# PI_SCH_HDMI.net
KiCad netlist of a schematic drawn in EasyEDA
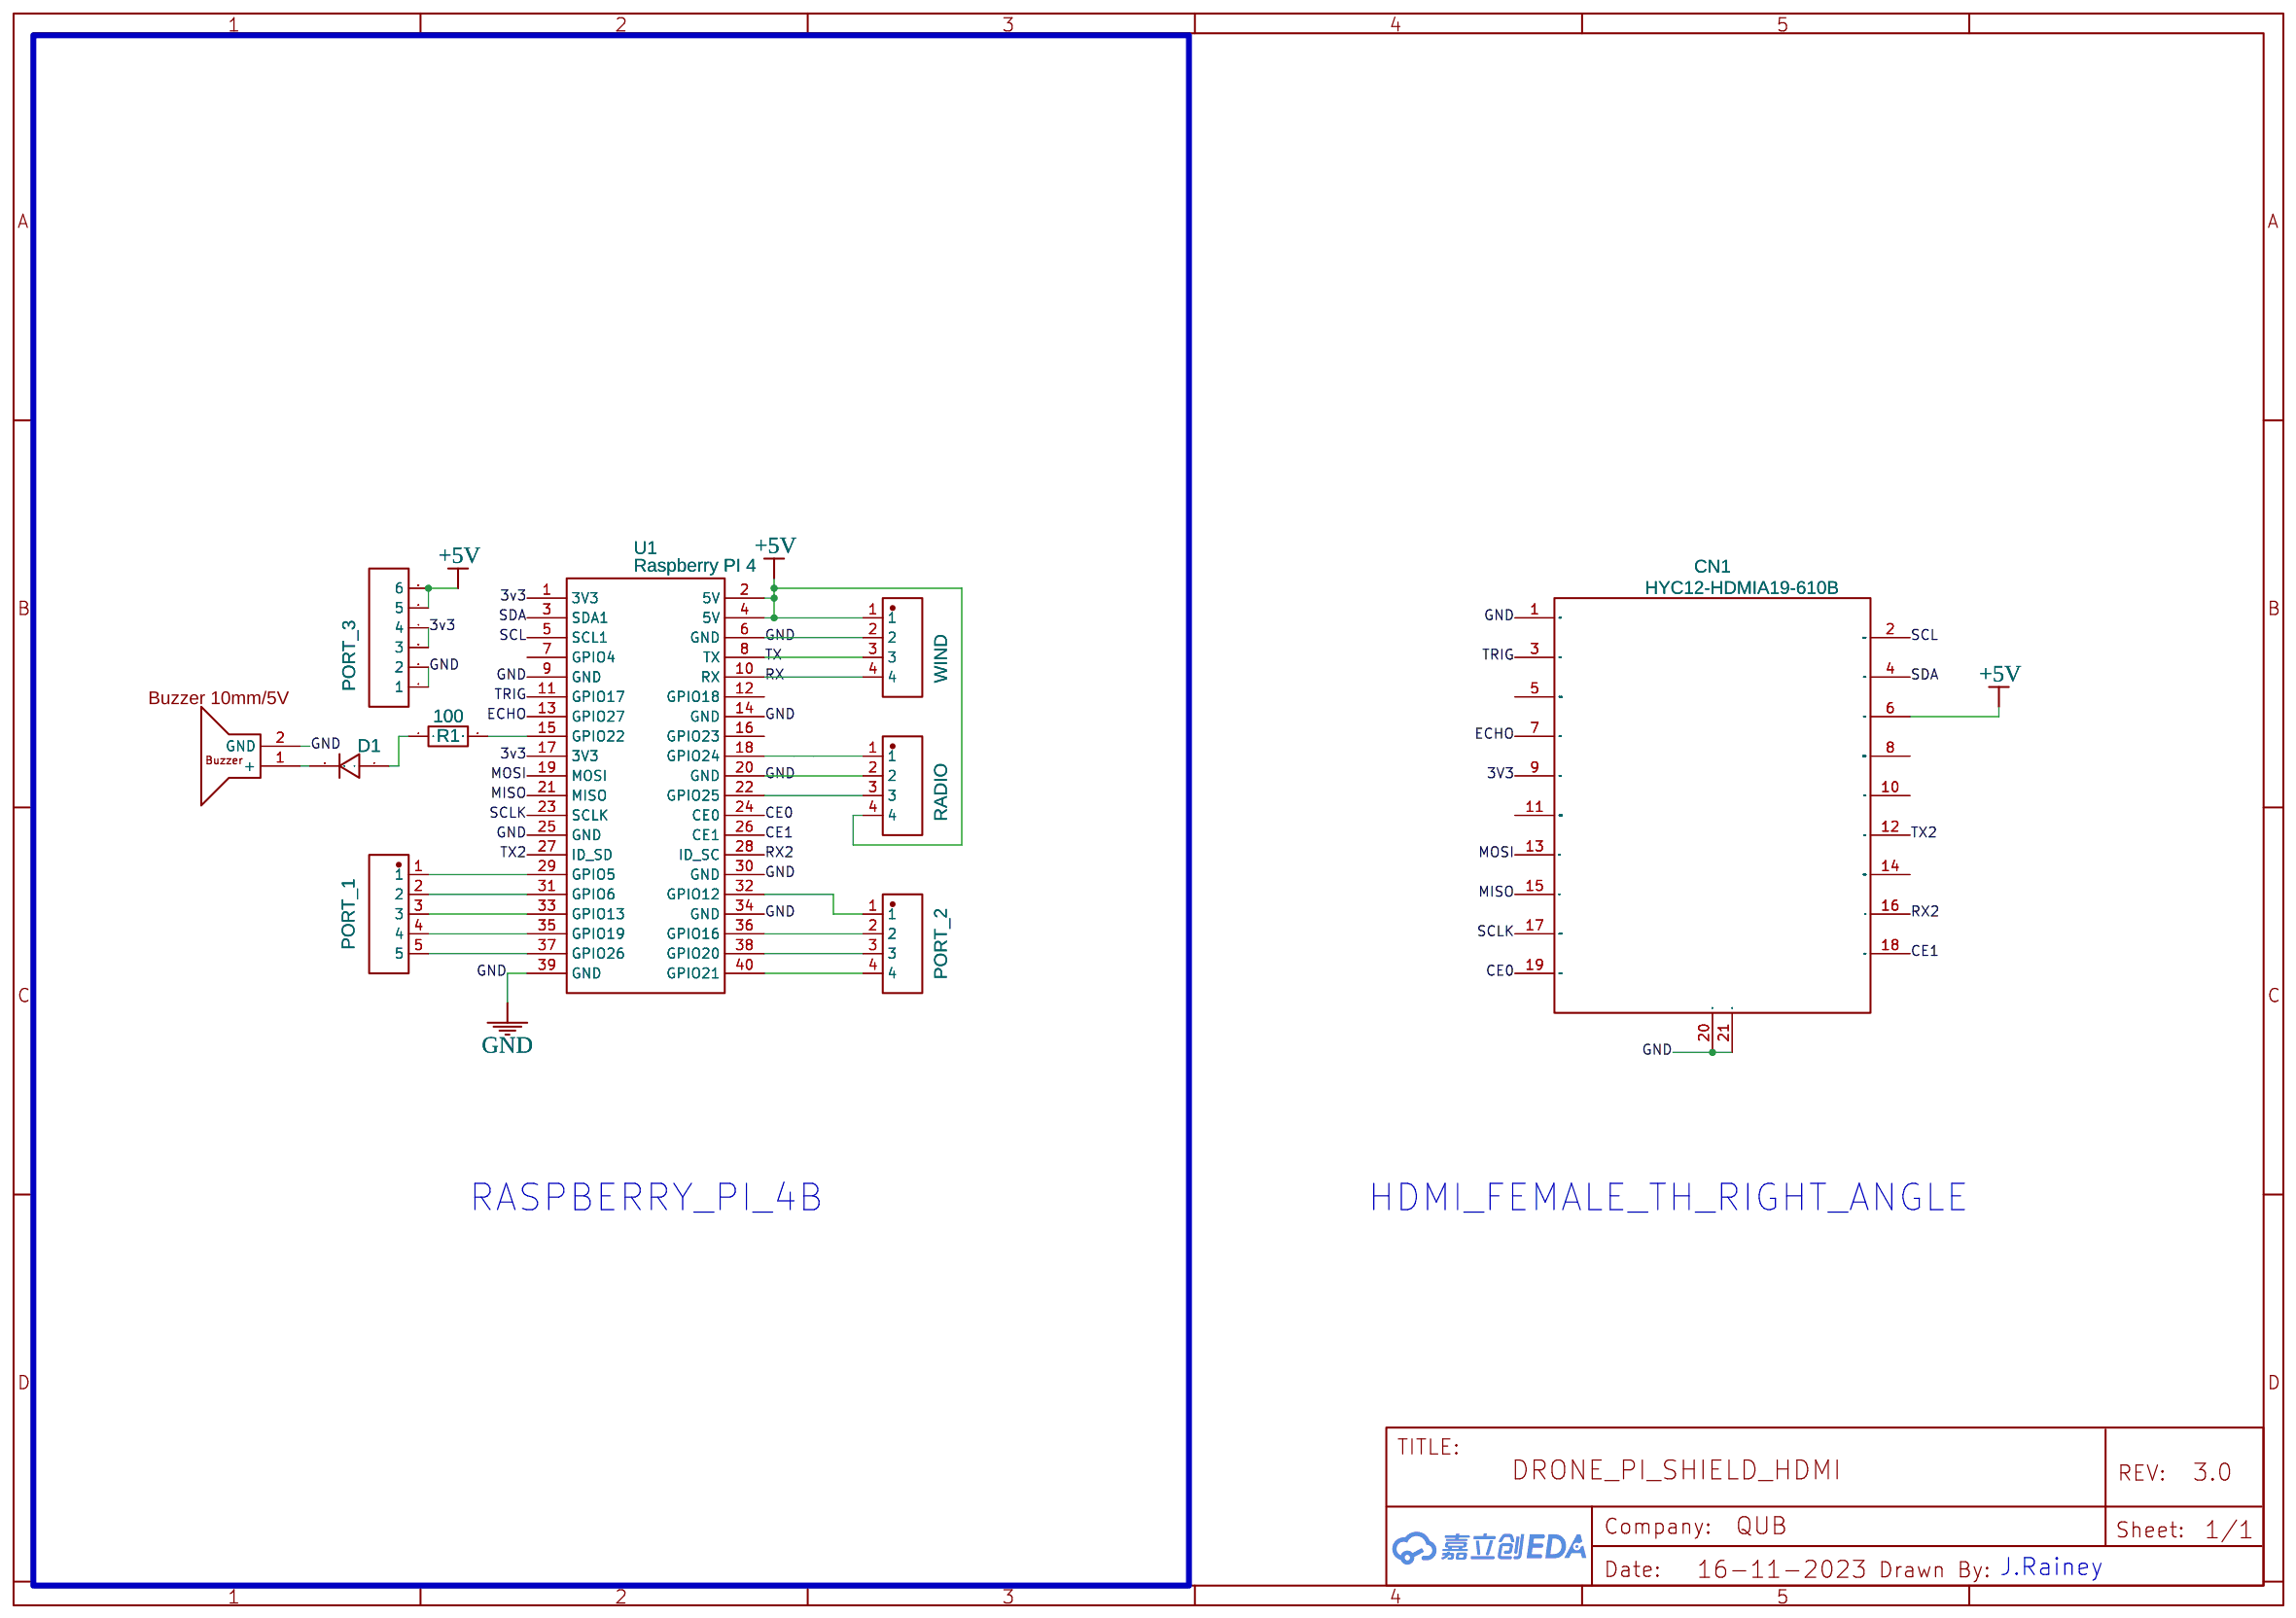
[diagram p0: schematic sheet]

(export (version "E")
  (design (tool "Eeschema 10.0.6"))
  (components
    (comp (ref "BUZZER1")
      (value "Buzzer 10mm/5V")
      (fields (field (name "BOM_Manufacturer Part") "BUZZER"))
      (libsource (lib "") (part "Buzzer 10mm/5V"))
    )
    (comp (ref "CN1")
      (value "HYC12-HDMIA19-610B")
      (fields (field (name "BOM_Supplier Part") "C711354"))
      (libsource (lib "") (part "HYC12-HDMIA19-610B"))
    )
    (comp (ref "D1")
      (value "1N4448")
      (fields (field (name "Manufacturer") "ST(先科)"))
      (libsource (lib "") (part "1N4448"))
    )
    (comp (ref "PORT_1")
      (value "PZ254V-11-05P")
      (fields (field (name "BOM_Supplier Part") "C492404"))
      (libsource (lib "") (part "PZ254V-11-05P"))
    )
    (comp (ref "PORT_2")
      (value "PZ254V-11-04P")
      (fields (field (name "BOM_Supplier Part") "C492403"))
      (libsource (lib "") (part "PZ254V-11-04P_2"))
    )
    (comp (ref "PORT_3")
      (value "HEADER-MALE-2.54_1X6")
      (fields
        (field (name "BOM_Manufacturer Part") "Header-Male-2.54_1x6")
        (field (name "BOM_Supplier Part") "C37208")
      )
      (libsource (lib "") (part "HEADER-MALE-2.54_1X6"))
    )
    (comp (ref "R1") (value "100") (libsource (lib "") (part "R_AXIAL-0.4_EU")))
    (comp (ref "RADIO")
      (value "PZ254V-11-04P")
      (fields (field (name "BOM_Supplier Part") "C492403"))
      (libsource (lib "") (part "PZ254V-11-04P"))
    )
    (comp (ref "U1") (value "Raspberry PI 4") (libsource (lib "") (part "Raspberry PI 4")))
    (comp (ref "WIND")
      (value "PZ254V-11-04P")
      (fields (field (name "BOM_Supplier Part") "C492403"))
      (libsource (lib "") (part "PZ254V-11-04P_1"))
    )
  )
  (nets
    (net (code "1") (name "+5V") (class "Default")
      (node (ref "CN1") (pin "6") (pinfunction "TMDS_Data_1-_6") (pintype "unspecified"))
      (node (ref "PORT_3") (pin "5") (pinfunction "5_5") (pintype "input"))
      (node (ref "PORT_3") (pin "6") (pinfunction "6_6") (pintype "input"))
      (node (ref "RADIO") (pin "4") (pinfunction "4_4") (pintype "unspecified"))
      (node (ref "U1") (pin "2") (pinfunction "5V_2") (pintype "unspecified"))
      (node (ref "U1") (pin "4") (pinfunction "5V_4") (pintype "unspecified"))
      (node (ref "WIND") (pin "1") (pinfunction "1_1") (pintype "unspecified"))
    )
    (net (code "2") (name "/3V3") (class "Default")
      (node (ref "CN1") (pin "9") (pinfunction "TMDS_Data_0-_9") (pintype "unspecified"))
    )
    (net (code "3") (name "/3v3") (class "Default")
      (node (ref "PORT_3") (pin "3") (pinfunction "3_3") (pintype "input"))
      (node (ref "PORT_3") (pin "4") (pinfunction "4_4") (pintype "input"))
      (node (ref "U1") (pin "1") (pinfunction "3V3_1") (pintype "unspecified"))
      (node (ref "U1") (pin "17") (pinfunction "3V3_17") (pintype "unspecified"))
    )
    (net (code "4") (name "/CE0") (class "Default")
      (node (ref "CN1") (pin "19") (pinfunction "Hot_Plug_Detect_19") (pintype "unspecified"))
      (node (ref "U1") (pin "24") (pinfunction "CE0_24") (pintype "unspecified"))
    )
    (net (code "5") (name "/CE1") (class "Default")
      (node (ref "CN1") (pin "18") (pinfunction "+5V_Power_18") (pintype "unspecified"))
      (node (ref "U1") (pin "26") (pinfunction "CE1_26") (pintype "unspecified"))
    )
    (net (code "6") (name "/ECHO") (class "Default")
      (node (ref "CN1") (pin "7") (pinfunction "TMDS_Data_0+_7") (pintype "unspecified"))
      (node (ref "U1") (pin "13") (pinfunction "GPIO27_13") (pintype "unspecified"))
    )
    (net (code "7") (name "/MISO") (class "Default")
      (node (ref "CN1") (pin "15") (pinfunction "SCL_15") (pintype "unspecified"))
      (node (ref "U1") (pin "21") (pinfunction "MISO_21") (pintype "unspecified"))
    )
    (net (code "8") (name "/MOSI") (class "Default")
      (node (ref "CN1") (pin "13") (pinfunction "CEC_13") (pintype "unspecified"))
      (node (ref "U1") (pin "19") (pinfunction "MOSI_19") (pintype "unspecified"))
    )
    (net (code "9") (name "/RX") (class "Default")
      (node (ref "U1") (pin "10") (pinfunction "RX_10") (pintype "unspecified"))
      (node (ref "WIND") (pin "4") (pinfunction "4_4") (pintype "unspecified"))
    )
    (net (code "10") (name "/RX2") (class "Default")
      (node (ref "CN1") (pin "16") (pinfunction "SDA_16") (pintype "unspecified"))
      (node (ref "U1") (pin "28") (pinfunction "ID_SC_28") (pintype "unspecified"))
    )
    (net (code "11") (name "/SCL") (class "Default")
      (node (ref "CN1") (pin "2") (pinfunction "TMDS_Data_2_Shield_2") (pintype "unspecified"))
      (node (ref "U1") (pin "5") (pinfunction "SCL1_5") (pintype "unspecified"))
    )
    (net (code "12") (name "/SCLK") (class "Default")
      (node (ref "CN1") (pin "17") (pinfunction "DDC/CEC_Ground_17") (pintype "unspecified"))
      (node (ref "U1") (pin "23") (pinfunction "SCLK_23") (pintype "unspecified"))
    )
    (net (code "13") (name "/SDA") (class "Default")
      (node (ref "CN1") (pin "4") (pinfunction "TMDS_Data_1+_4") (pintype "unspecified"))
      (node (ref "U1") (pin "3") (pinfunction "SDA1_3") (pintype "unspecified"))
    )
    (net (code "14") (name "/TRIG") (class "Default")
      (node (ref "CN1") (pin "3") (pinfunction "TMDS_Data_2-_3") (pintype "unspecified"))
      (node (ref "U1") (pin "11") (pinfunction "GPIO17_11") (pintype "unspecified"))
    )
    (net (code "15") (name "/TX") (class "Default")
      (node (ref "U1") (pin "8") (pinfunction "TX_8") (pintype "unspecified"))
      (node (ref "WIND") (pin "3") (pinfunction "3_3") (pintype "unspecified"))
    )
    (net (code "16") (name "/TX2") (class "Default")
      (node (ref "CN1") (pin "12") (pinfunction "TMDS_Clock-_12") (pintype "unspecified"))
      (node (ref "U1") (pin "27") (pinfunction "ID_SD_27") (pintype "unspecified"))
    )
    (net (code "17") (name "GND") (class "Default")
      (node (ref "BUZZER1") (pin "2") (pinfunction "GND_2") (pintype "unspecified"))
      (node (ref "CN1") (pin "1") (pinfunction "TMDS_Data_2+_1") (pintype "unspecified"))
      (node (ref "CN1") (pin "20") (pinfunction "EH_20") (pintype "unspecified"))
      (node (ref "CN1") (pin "21") (pinfunction "EH_21") (pintype "unspecified"))
      (node (ref "PORT_3") (pin "1") (pinfunction "1_1") (pintype "input"))
      (node (ref "PORT_3") (pin "2") (pinfunction "2_2") (pintype "input"))
      (node (ref "RADIO") (pin "2") (pinfunction "2_2") (pintype "unspecified"))
      (node (ref "U1") (pin "14") (pinfunction "GND_14") (pintype "unspecified"))
      (node (ref "U1") (pin "20") (pinfunction "GND_20") (pintype "unspecified"))
      (node (ref "U1") (pin "25") (pinfunction "GND_25") (pintype "unspecified"))
      (node (ref "U1") (pin "30") (pinfunction "GND_30") (pintype "unspecified"))
      (node (ref "U1") (pin "34") (pinfunction "GND_34") (pintype "unspecified"))
      (node (ref "U1") (pin "39") (pinfunction "GND_39") (pintype "unspecified"))
      (node (ref "U1") (pin "6") (pinfunction "GND_6") (pintype "unspecified"))
      (node (ref "U1") (pin "9") (pinfunction "GND_9") (pintype "unspecified"))
      (node (ref "WIND") (pin "2") (pinfunction "2_2") (pintype "unspecified"))
    )
    (net (code "18") (name "Net-(BUZZER1-+)") (class "Default")
      (node (ref "BUZZER1") (pin "1") (pinfunction "+_1") (pintype "unspecified"))
      (node (ref "D1") (pin "2") (pinfunction "K_2") (pintype "unspecified"))
    )
    (net (code "19") (name "Net-(D1-A)") (class "Default")
      (node (ref "D1") (pin "1") (pinfunction "A_1") (pintype "unspecified"))
      (node (ref "R1") (pin "1") (pinfunction "1_1") (pintype "unspecified"))
    )
    (net (code "20") (name "Net-(U1-GPIO5)") (class "Default")
      (node (ref "PORT_1") (pin "1") (pinfunction "1_1") (pintype "unspecified"))
      (node (ref "U1") (pin "29") (pinfunction "GPIO5_29") (pintype "unspecified"))
    )
    (net (code "21") (name "Net-(U1-GPIO6)") (class "Default")
      (node (ref "PORT_1") (pin "2") (pinfunction "2_2") (pintype "unspecified"))
      (node (ref "U1") (pin "31") (pinfunction "GPIO6_31") (pintype "unspecified"))
    )
    (net (code "22") (name "Net-(U1-GPIO12)") (class "Default")
      (node (ref "PORT_2") (pin "1") (pinfunction "1_1") (pintype "unspecified"))
      (node (ref "U1") (pin "32") (pinfunction "GPIO12_32") (pintype "unspecified"))
    )
    (net (code "23") (name "Net-(U1-GPIO13)") (class "Default")
      (node (ref "PORT_1") (pin "3") (pinfunction "3_3") (pintype "unspecified"))
      (node (ref "U1") (pin "33") (pinfunction "GPIO13_33") (pintype "unspecified"))
    )
    (net (code "24") (name "Net-(U1-GPIO16)") (class "Default")
      (node (ref "PORT_2") (pin "2") (pinfunction "2_2") (pintype "unspecified"))
      (node (ref "U1") (pin "36") (pinfunction "GPIO16_36") (pintype "unspecified"))
    )
    (net (code "25") (name "Net-(U1-GPIO19)") (class "Default")
      (node (ref "PORT_1") (pin "4") (pinfunction "4_4") (pintype "unspecified"))
      (node (ref "U1") (pin "35") (pinfunction "GPIO19_35") (pintype "unspecified"))
    )
    (net (code "26") (name "Net-(U1-GPIO20)") (class "Default")
      (node (ref "PORT_2") (pin "3") (pinfunction "3_3") (pintype "unspecified"))
      (node (ref "U1") (pin "38") (pinfunction "GPIO20_38") (pintype "unspecified"))
    )
    (net (code "27") (name "Net-(U1-GPIO21)") (class "Default")
      (node (ref "PORT_2") (pin "4") (pinfunction "4_4") (pintype "unspecified"))
      (node (ref "U1") (pin "40") (pinfunction "GPIO21_40") (pintype "unspecified"))
    )
    (net (code "28") (name "Net-(U1-GPIO22)") (class "Default")
      (node (ref "R1") (pin "2") (pinfunction "2_2") (pintype "unspecified"))
      (node (ref "U1") (pin "15") (pinfunction "GPIO22_15") (pintype "unspecified"))
    )
    (net (code "29") (name "Net-(U1-GPIO24)") (class "Default")
      (node (ref "RADIO") (pin "1") (pinfunction "1_1") (pintype "unspecified"))
      (node (ref "U1") (pin "18") (pinfunction "GPIO24_18") (pintype "unspecified"))
    )
    (net (code "30") (name "Net-(U1-GPIO25)") (class "Default")
      (node (ref "RADIO") (pin "3") (pinfunction "3_3") (pintype "unspecified"))
      (node (ref "U1") (pin "22") (pinfunction "GPIO25_22") (pintype "unspecified"))
    )
    (net (code "31") (name "Net-(U1-GPIO26)") (class "Default")
      (node (ref "PORT_1") (pin "5") (pinfunction "5_5") (pintype "unspecified"))
      (node (ref "U1") (pin "37") (pinfunction "GPIO26_37") (pintype "unspecified"))
    )
    (net (code "32") (name "unconnected-(CN1-Reserved_(N.C.)-Pad14)") (class "Default")
      (node (ref "CN1") (pin "14") (pinfunction "Reserved_(N.C.)_14") (pintype "unspecified"))
    )
    (net (code "33") (name "unconnected-(CN1-TMDS_Clock+-Pad10)") (class "Default")
      (node (ref "CN1") (pin "10") (pinfunction "TMDS_Clock+_10") (pintype "unspecified"))
    )
    (net (code "34") (name "unconnected-(CN1-TMDS_Clock_Shield-Pad11)") (class "Default")
      (node (ref "CN1") (pin "11") (pinfunction "TMDS_Clock_Shield_11") (pintype "unspecified"))
    )
    (net (code "35") (name "unconnected-(CN1-TMDS_Data_0_Shield-Pad8)") (class "Default")
      (node (ref "CN1") (pin "8") (pinfunction "TMDS_Data_0_Shield_8") (pintype "unspecified"))
    )
    (net (code "36") (name "unconnected-(CN1-TMDS_Data_1_Shield-Pad5)") (class "Default")
      (node (ref "CN1") (pin "5") (pinfunction "TMDS_Data_1_Shield_5") (pintype "unspecified"))
    )
    (net (code "37") (name "unconnected-(U1-GPIO4-Pad7)") (class "Default")
      (node (ref "U1") (pin "7") (pinfunction "GPIO4_7") (pintype "unspecified"))
    )
    (net (code "38") (name "unconnected-(U1-GPIO18-Pad12)") (class "Default")
      (node (ref "U1") (pin "12") (pinfunction "GPIO18_12") (pintype "unspecified"))
    )
    (net (code "39") (name "unconnected-(U1-GPIO23-Pad16)") (class "Default")
      (node (ref "U1") (pin "16") (pinfunction "GPIO23_16") (pintype "unspecified"))
    )
  )
)
